# servo.net
KiCad netlist of a schematic drawn in Altium Designer
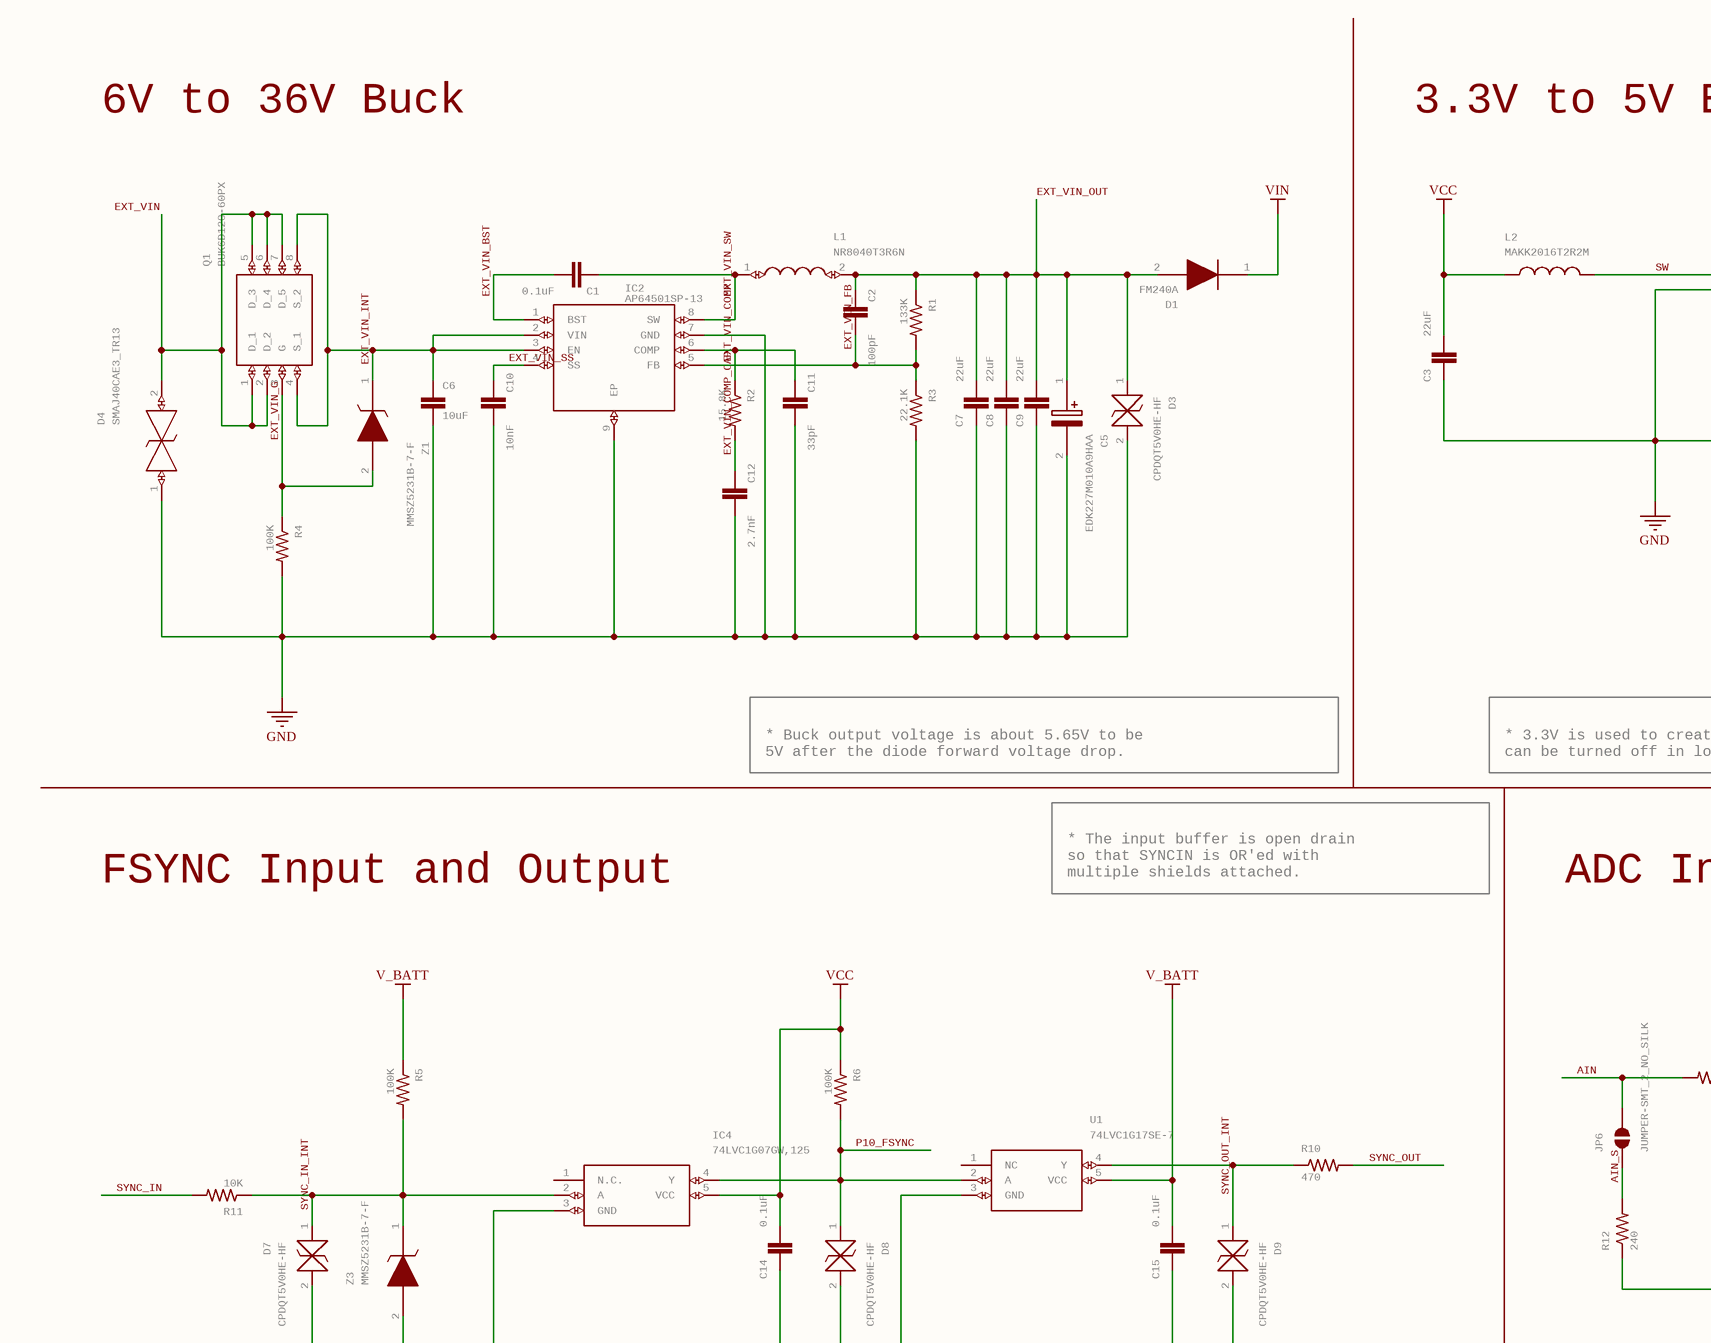
[diagram p0: servo.SchDoc, top left]
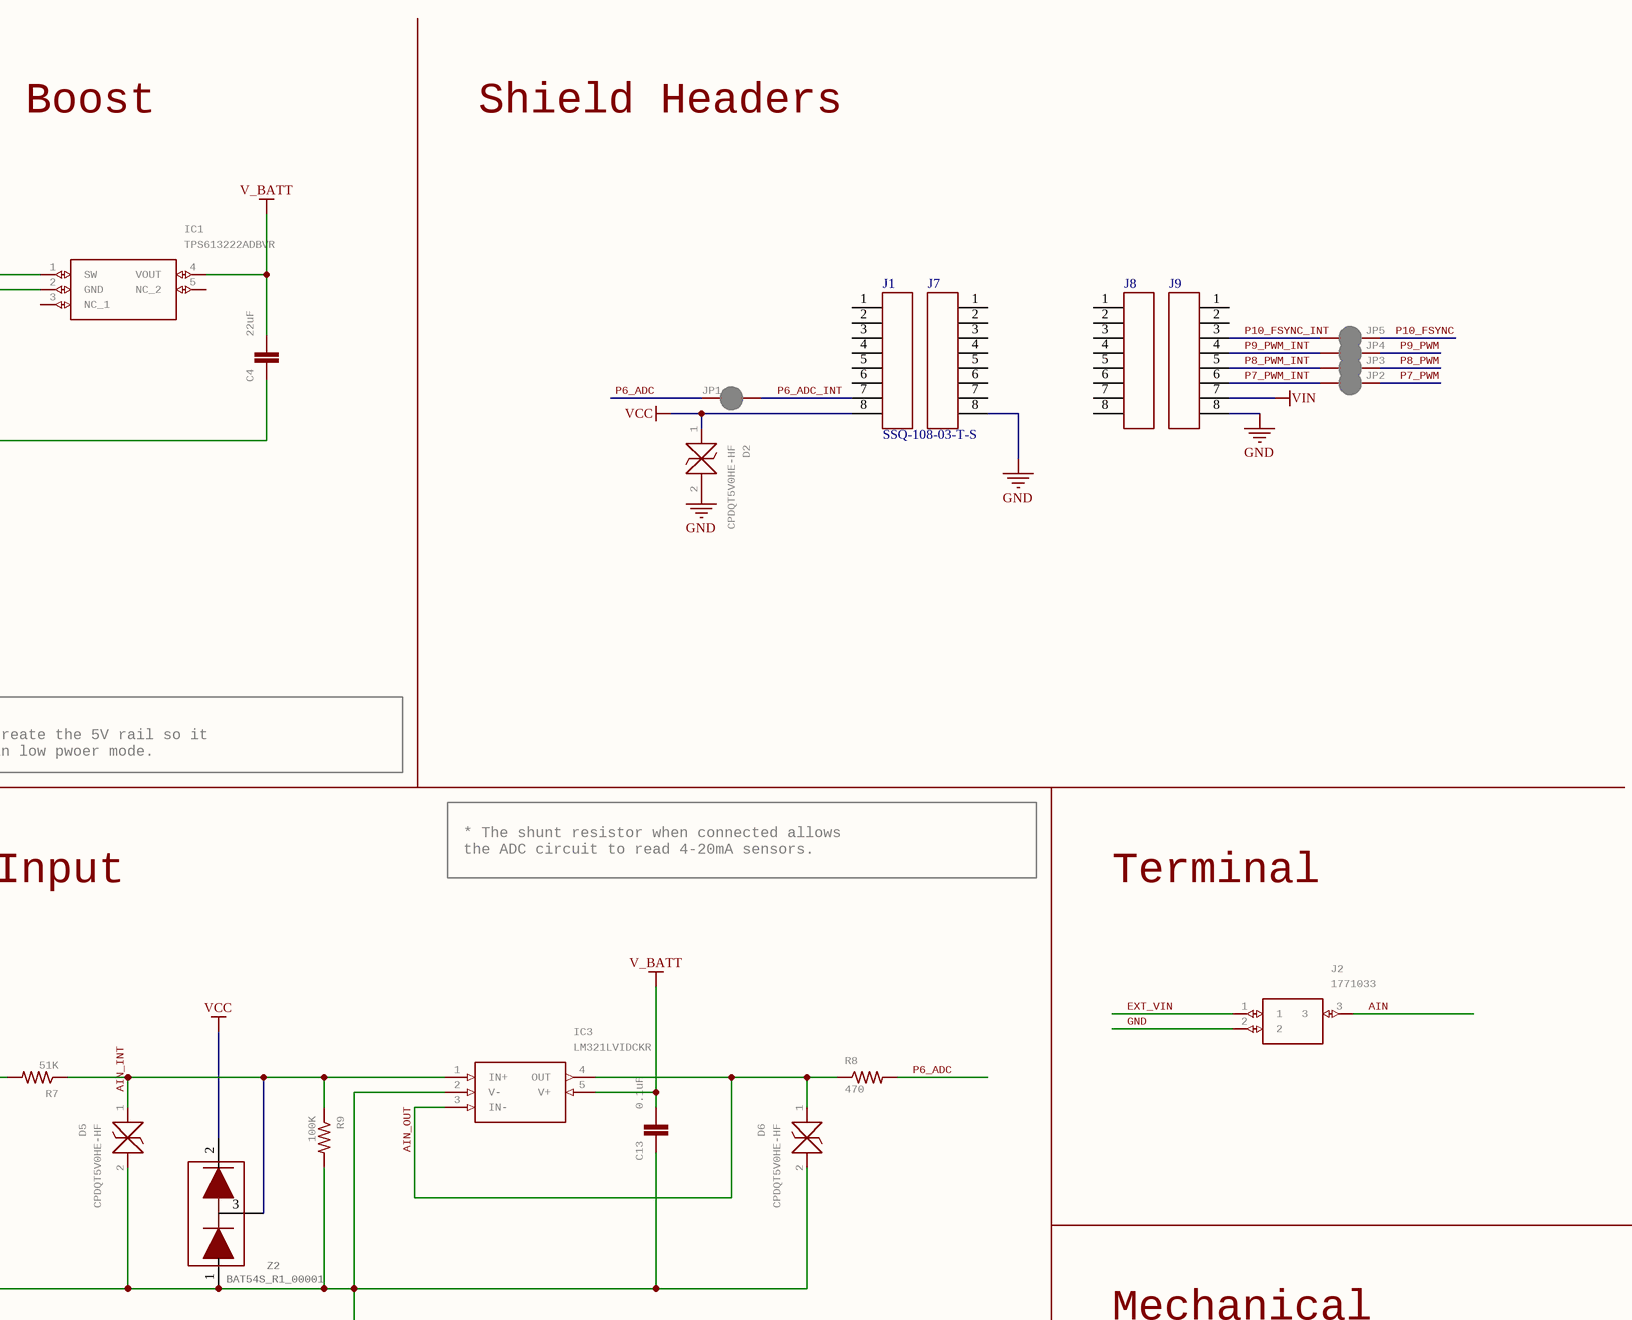
[diagram p1: servo.SchDoc, top right]
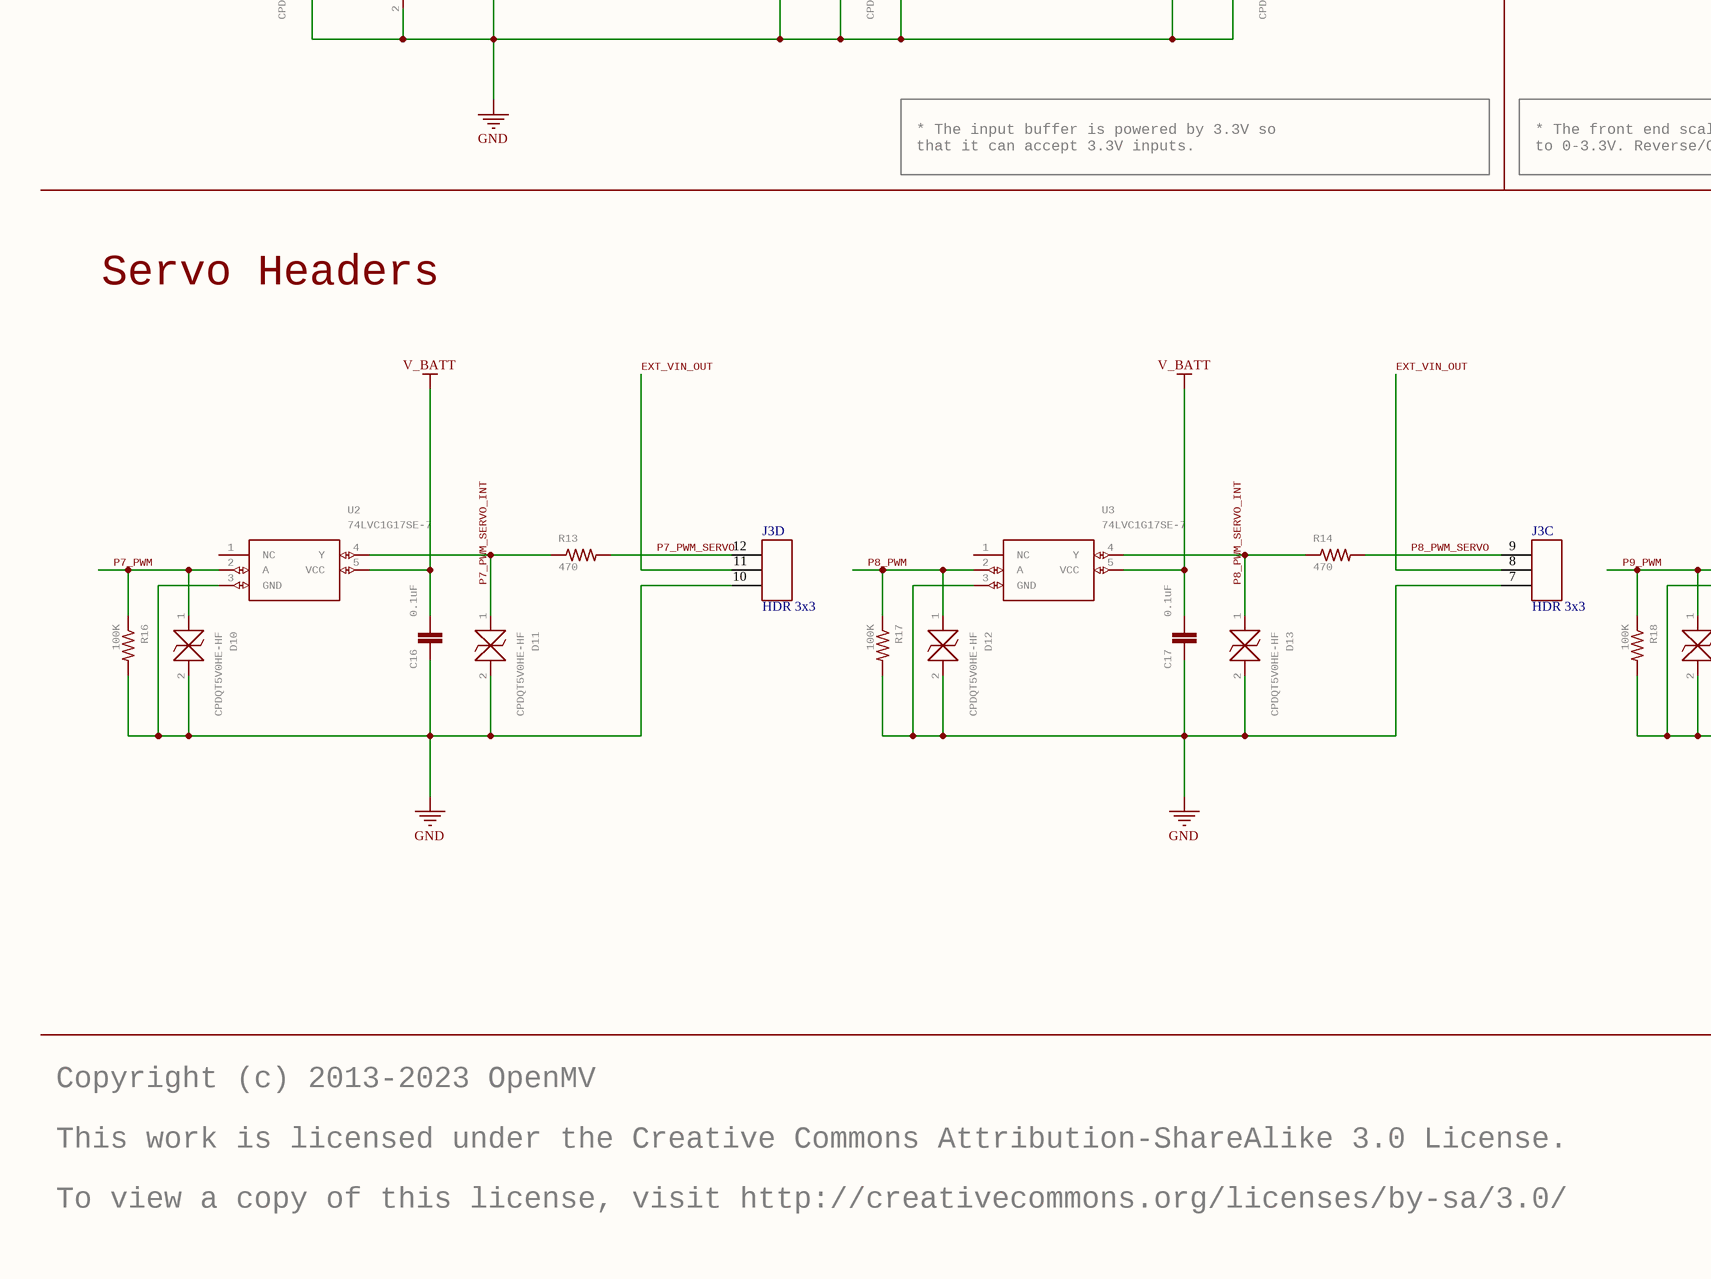
[diagram p2: servo.SchDoc, bottom left]
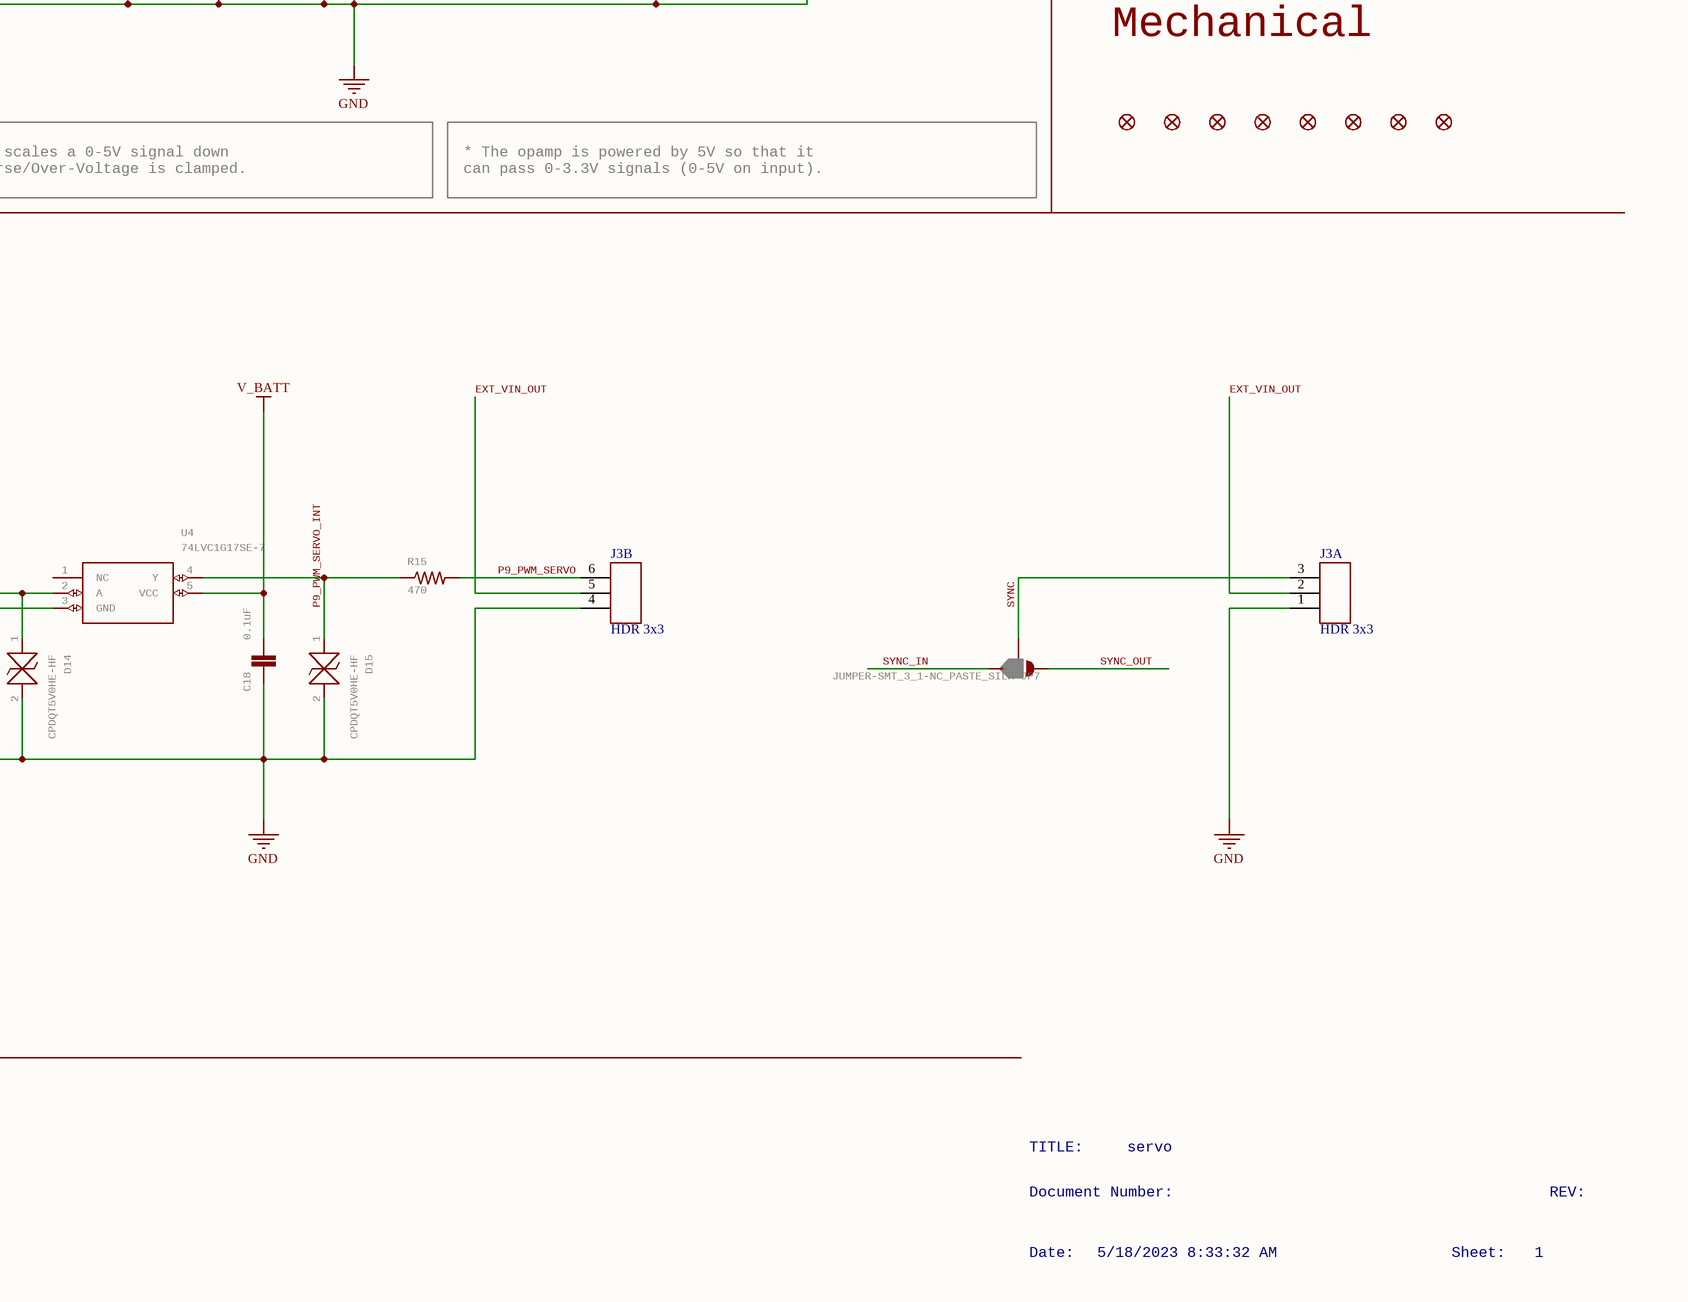
[diagram p3: servo.SchDoc, bottom right]

(export (version "E")
  (design (tool "Eeschema 10.0.6"))
  (components
    (comp (ref "C1")
      (value "0.1uF")
      (footprint "0402-CAP")
      (description "0402 (1005 Metric) Nick Garner - TeleSense")
      (fields (field (name "MPN") "GRM155R71H104KE14D"))
      (libsource (lib "") (part "CAP_0402_1"))
    )
    (comp (ref "C2")
      (value "100pF")
      (footprint "0402-CAP")
      (description "0402 (1005 Metric) Nick Garner - TeleSense")
      (fields (field (name "MPN") "CC0402JRNPO9BN101"))
      (libsource (lib "") (part "CAP_0402_2"))
    )
    (comp (ref "C3")
      (value "22uF")
      (footprint "0805-CAP")
      (fields (field (name "MPN") "CL21A226MQQNNNE"))
      (libsource (lib "SparkFun-Capacitors") (part "22UF-0805-6.3V-20%"))
    )
    (comp (ref "C4")
      (value "22uF")
      (footprint "0805-CAP")
      (fields (field (name "MPN") "CL21A226MQQNNNE"))
      (libsource (lib "SparkFun-Capacitors") (part "22UF-0805-6.3V-20%"))
    )
    (comp (ref "C5")
      (value "EDK227M010A9HAA")
      (footprint "CAPAE660X800N")
      (fields (field (name "MOUSER_PART_NUMBER") "80-EDK227M010A9HAA"))
      (libsource (lib "EDK227M010A9HAA") (part "EDK227M010A9HAA"))
    )
    (comp (ref "C6")
      (value "10uF")
      (footprint "C0805")
      (description "CAPACITOR, European symbol")
      (fields (field (name "MPN") "GRM21BR61H106KE43K"))
      (libsource (lib "rcl") (part "C-EUC0805"))
    )
    (comp (ref "C7")
      (value "22uF")
      (footprint "0805-CAP")
      (fields (field (name "MPN") "CL21A226MQQNNNE"))
      (libsource (lib "SparkFun-Capacitors") (part "22UF-0805-6.3V-20%"))
    )
    (comp (ref "C8")
      (value "22uF")
      (footprint "0805-CAP")
      (fields (field (name "MPN") "CL21A226MQQNNNE"))
      (libsource (lib "SparkFun-Capacitors") (part "22UF-0805-6.3V-20%"))
    )
    (comp (ref "C9")
      (value "22uF")
      (footprint "0805-CAP")
      (fields (field (name "MPN") "CL21A226MQQNNNE"))
      (libsource (lib "SparkFun-Capacitors") (part "22UF-0805-6.3V-20%"))
    )
    (comp (ref "C10")
      (value "10nF")
      (footprint "0402-CAP")
      (description "0402 (1005 Metric) Nick Garner - TeleSense")
      (fields (field (name "MPN") "CL05B103KB5NNNC"))
      (libsource (lib "") (part "CAP_0402_2"))
    )
    (comp (ref "C11")
      (value "33pF")
      (footprint "0402-CAP")
      (description "0402 (1005 Metric) Nick Garner - TeleSense")
      (fields (field (name "MPN") "04025A330JAT2A"))
      (libsource (lib "") (part "CAP_0402_2"))
    )
    (comp (ref "C12")
      (value "2.7nF")
      (footprint "0402-CAP")
      (description "0402 (1005 Metric) Nick Garner - TeleSense")
      (fields (field (name "MPN") "GCM155R71H272KA37J"))
      (libsource (lib "") (part "CAP_0402_2"))
    )
    (comp (ref "C13")
      (value "0.1uF")
      (footprint "0402-CAP")
      (description "0402 (1005 Metric) Nick Garner - TeleSense")
      (fields (field (name "MPN") "GRM155R71H104KE14D"))
      (libsource (lib "0402") (part "CAP_0402"))
    )
    (comp (ref "C14")
      (value "0.1uF")
      (footprint "0402-CAP")
      (description "0402 (1005 Metric) Nick Garner - TeleSense")
      (fields (field (name "MPN") "GRM155R71H104KE14D"))
      (libsource (lib "0402") (part "CAP_0402"))
    )
    (comp (ref "C15")
      (value "0.1uF")
      (footprint "0402-CAP")
      (description "0402 (1005 Metric) Nick Garner - TeleSense")
      (fields (field (name "MPN") "GRM155R71H104KE14D"))
      (libsource (lib "0402") (part "CAP_0402"))
    )
    (comp (ref "C16")
      (value "0.1uF")
      (footprint "0402-CAP")
      (description "0402 (1005 Metric) Nick Garner - TeleSense")
      (fields (field (name "MPN") "GRM155R71H104KE14D"))
      (libsource (lib "0402") (part "CAP_0402"))
    )
    (comp (ref "C17")
      (value "0.1uF")
      (footprint "0402-CAP")
      (description "0402 (1005 Metric) Nick Garner - TeleSense")
      (fields (field (name "MPN") "GRM155R71H104KE14D"))
      (libsource (lib "0402") (part "CAP_0402"))
    )
    (comp (ref "C18")
      (value "0.1uF")
      (footprint "0402-CAP")
      (description "0402 (1005 Metric) Nick Garner - TeleSense")
      (fields (field (name "MPN") "GRM155R71H104KE14D"))
      (libsource (lib "0402") (part "CAP_0402"))
    )
    (comp (ref "D1")
      (value "FM240A")
      (footprint "DIOM5025X231N")
      (description "Diodes - General Purpose, Power, Switching GP Si Rectifier SMB,2A,40V   Source:  Datasheet")
      (fields (field (name "MOUSER_PART_NUMBER") "583-FM240A"))
      (libsource (lib "FM240A") (part "FM240A"))
    )
    (comp (ref "D2")
      (value "CPDQT5V0HE-HF")
      (footprint "CPDQT5V0HEHF")
      (description "ESD Suppressors / TVS Diodes DIODE ESD 5VWM 65W 0402/SOD-923F   Source:  Datasheet")
      (fields (field (name "MOUSER_PART_NUMBER") "MOUSER_PART_NUMBER"))
      (libsource (lib "CPDQT5V0HE-HF") (part "CPDQT5V0HE-HF"))
    )
    (comp (ref "D3")
      (value "CPDQT5V0HE-HF")
      (footprint "CPDQT5V0HEHF")
      (description "ESD Suppressors / TVS Diodes DIODE ESD 5VWM 65W 0402/SOD-923F   Source:  Datasheet")
      (fields (field (name "MOUSER_PART_NUMBER") "MOUSER_PART_NUMBER"))
      (libsource (lib "CPDQT5V0HE-HF") (part "CPDQT5V0HE-HF"))
    )
    (comp (ref "D4")
      (value "SMAJ40CAE3_TR13")
      (footprint "SMAJ40CAE3TR13")
      (description "ESD Suppressors / TVS Diodes TVS   Source:  Datasheet")
      (fields
        (field (name "MANUFACTURER_PART_NUMBER") "SMAJ40CAe3/TR13")
        (field (name "MOUSER_PART_NUMBER") "494-SMAJ40CAE3/TR13")
      )
      (libsource (lib "SMAJ40CAe3_TR13") (part "SMAJ40CAE3_TR13"))
    )
    (comp (ref "D5")
      (value "CPDQT5V0HE-HF")
      (footprint "CPDQT5V0HEHF")
      (description "ESD Suppressors / TVS Diodes DIODE ESD 5VWM 65W 0402/SOD-923F   Source:  Datasheet")
      (fields (field (name "MOUSER_PART_NUMBER") "MOUSER_PART_NUMBER"))
      (libsource (lib "CPDQT5V0HE-HF") (part "CPDQT5V0HE-HF"))
    )
    (comp (ref "D6")
      (value "CPDQT5V0HE-HF")
      (footprint "CPDQT5V0HEHF")
      (description "ESD Suppressors / TVS Diodes DIODE ESD 5VWM 65W 0402/SOD-923F   Source:  Datasheet")
      (fields (field (name "MOUSER_PART_NUMBER") "MOUSER_PART_NUMBER"))
      (libsource (lib "CPDQT5V0HE-HF") (part "CPDQT5V0HE-HF"))
    )
    (comp (ref "D7")
      (value "CPDQT5V0HE-HF")
      (footprint "CPDQT5V0HEHF")
      (description "ESD Suppressors / TVS Diodes DIODE ESD 5VWM 65W 0402/SOD-923F   Source:  Datasheet")
      (fields (field (name "MOUSER_PART_NUMBER") "MOUSER_PART_NUMBER"))
      (libsource (lib "CPDQT5V0HE-HF") (part "CPDQT5V0HE-HF"))
    )
    (comp (ref "D8")
      (value "CPDQT5V0HE-HF")
      (footprint "CPDQT5V0HEHF")
      (description "ESD Suppressors / TVS Diodes DIODE ESD 5VWM 65W 0402/SOD-923F   Source:  Datasheet")
      (fields (field (name "MOUSER_PART_NUMBER") "MOUSER_PART_NUMBER"))
      (libsource (lib "CPDQT5V0HE-HF") (part "CPDQT5V0HE-HF"))
    )
    (comp (ref "D9")
      (value "CPDQT5V0HE-HF")
      (footprint "CPDQT5V0HEHF")
      (description "ESD Suppressors / TVS Diodes DIODE ESD 5VWM 65W 0402/SOD-923F   Source:  Datasheet")
      (fields (field (name "MOUSER_PART_NUMBER") "MOUSER_PART_NUMBER"))
      (libsource (lib "CPDQT5V0HE-HF") (part "CPDQT5V0HE-HF"))
    )
    (comp (ref "D10")
      (value "CPDQT5V0HE-HF")
      (footprint "CPDQT5V0HEHF")
      (description "ESD Suppressors / TVS Diodes DIODE ESD 5VWM 65W 0402/SOD-923F   Source:  Datasheet")
      (fields (field (name "MOUSER_PART_NUMBER") "MOUSER_PART_NUMBER"))
      (libsource (lib "CPDQT5V0HE-HF") (part "CPDQT5V0HE-HF"))
    )
    (comp (ref "D11")
      (value "CPDQT5V0HE-HF")
      (footprint "CPDQT5V0HEHF")
      (description "ESD Suppressors / TVS Diodes DIODE ESD 5VWM 65W 0402/SOD-923F   Source:  Datasheet")
      (fields (field (name "MOUSER_PART_NUMBER") "MOUSER_PART_NUMBER"))
      (libsource (lib "CPDQT5V0HE-HF") (part "CPDQT5V0HE-HF"))
    )
    (comp (ref "D12")
      (value "CPDQT5V0HE-HF")
      (footprint "CPDQT5V0HEHF")
      (description "ESD Suppressors / TVS Diodes DIODE ESD 5VWM 65W 0402/SOD-923F   Source:  Datasheet")
      (fields (field (name "MOUSER_PART_NUMBER") "MOUSER_PART_NUMBER"))
      (libsource (lib "CPDQT5V0HE-HF") (part "CPDQT5V0HE-HF"))
    )
    (comp (ref "D13")
      (value "CPDQT5V0HE-HF")
      (footprint "CPDQT5V0HEHF")
      (description "ESD Suppressors / TVS Diodes DIODE ESD 5VWM 65W 0402/SOD-923F   Source:  Datasheet")
      (fields (field (name "MOUSER_PART_NUMBER") "MOUSER_PART_NUMBER"))
      (libsource (lib "CPDQT5V0HE-HF") (part "CPDQT5V0HE-HF"))
    )
    (comp (ref "D14")
      (value "CPDQT5V0HE-HF")
      (footprint "CPDQT5V0HEHF")
      (description "ESD Suppressors / TVS Diodes DIODE ESD 5VWM 65W 0402/SOD-923F   Source:  Datasheet")
      (fields (field (name "MOUSER_PART_NUMBER") "MOUSER_PART_NUMBER"))
      (libsource (lib "CPDQT5V0HE-HF") (part "CPDQT5V0HE-HF"))
    )
    (comp (ref "D15")
      (value "CPDQT5V0HE-HF")
      (footprint "CPDQT5V0HEHF")
      (description "ESD Suppressors / TVS Diodes DIODE ESD 5VWM 65W 0402/SOD-923F   Source:  Datasheet")
      (fields (field (name "MOUSER_PART_NUMBER") "MOUSER_PART_NUMBER"))
      (libsource (lib "CPDQT5V0HE-HF") (part "CPDQT5V0HE-HF"))
    )
    (comp (ref "FD1")
      (value "FIDUCIAL1X2")
      (footprint "FIDUCIAL-1X2")
      (fields (field (name "LIBRARYNAME") "SparkFun-Aesthetics"))
      (libsource (lib "SparkFun-Aesthetics") (part "FIDUCIAL1X2"))
    )
    (comp (ref "FD2")
      (value "FIDUCIAL1X2")
      (footprint "FIDUCIAL-1X2")
      (fields (field (name "LIBRARYNAME") "SparkFun-Aesthetics"))
      (libsource (lib "SparkFun-Aesthetics") (part "FIDUCIAL1X2"))
    )
    (comp (ref "FD3")
      (value "FIDUCIAL1X2")
      (footprint "FIDUCIAL-1X2")
      (fields (field (name "LIBRARYNAME") "SparkFun-Aesthetics"))
      (libsource (lib "SparkFun-Aesthetics") (part "FIDUCIAL1X2"))
    )
    (comp (ref "FD4")
      (value "FIDUCIAL1X2")
      (footprint "FIDUCIAL-1X2")
      (fields (field (name "LIBRARYNAME") "SparkFun-Aesthetics"))
      (libsource (lib "SparkFun-Aesthetics") (part "FIDUCIAL1X2"))
    )
    (comp (ref "FD5")
      (value "FIDUCIAL1X2")
      (footprint "FIDUCIAL-1X2")
      (fields (field (name "LIBRARYNAME") "SparkFun-Aesthetics"))
      (libsource (lib "SparkFun-Aesthetics") (part "FIDUCIAL1X2"))
    )
    (comp (ref "FD6")
      (value "FIDUCIAL1X2")
      (footprint "FIDUCIAL-1X2")
      (fields (field (name "LIBRARYNAME") "SparkFun-Aesthetics"))
      (libsource (lib "SparkFun-Aesthetics") (part "FIDUCIAL1X2"))
    )
    (comp (ref "FD7")
      (value "FIDUCIAL1X2")
      (footprint "FIDUCIAL-1X2")
      (fields (field (name "LIBRARYNAME") "SparkFun-Aesthetics"))
      (libsource (lib "SparkFun-Aesthetics") (part "FIDUCIAL1X2"))
    )
    (comp (ref "FD8")
      (value "FIDUCIAL1X2")
      (footprint "FIDUCIAL-1X2")
      (fields (field (name "LIBRARYNAME") "SparkFun-Aesthetics"))
      (libsource (lib "SparkFun-Aesthetics") (part "FIDUCIAL1X2"))
    )
    (comp (ref "IC1")
      (value "TPS613222ADBVR")
      (footprint "SOT95P280X145-5N")
      (description "6-uA Quiescent Current, 1.8-A Switch Current Boost Converter   Source:  Datasheet")
      (fields (field (name "MOUSER_PART_NUMBER") "595-TPS613222ADBVR"))
      (libsource (lib "TPS613222ADBVR") (part "TPS613222ADBVR"))
    )
    (comp (ref "IC2")
      (value "AP64501SP-13")
      (footprint "SOIC127P600X163-9N")
      (fields (field (name "MOUSER_PART_NUMBER") "621-AP64501SP-13"))
      (libsource (lib "AP64501SP-13") (part "AP64501SP-13"))
    )
    (comp (ref "IC3")
      (value "LM321LVIDCKR")
      (footprint "SOT65P210X110-5N")
      (description "1-Channel industry standard low voltage operational amplifier   Source:  Datasheet")
      (fields (field (name "MOUSER_PART_NUMBER") "595-LM321LVIDCKR"))
      (libsource (lib "LM321LVIDCKR") (part "LM321LVIDCKR"))
    )
    (comp (ref "IC4")
      (value "74LVC1G07GW,125")
      (footprint "SOT65P212X110-5N")
      (description "74LVC1G07 - Buffer with open-drain output@en-us   Source:  Datasheet")
      (fields (field (name "MOUSER_PART_NUMBER") "771-74LVC1G07GW-G"))
      (libsource (lib "74LVC1G07GW_125") (part "74LVC1G07GW,125"))
    )
    (comp (ref "J1") (value "SSQ-108-03-T-S") (footprint "HDR_1X8") (libsource (lib "pir") (part "HDR_1X8")))
    (comp (ref "J2")
      (value "1771033")
      (footprint "1771033")
      (fields (field (name "MOUSER_PART_NUMBER") "651-1771033"))
      (libsource (lib "1771033") (part "1771033"))
    )
    (comp (ref "J3")
      (value "HDR 3x3")
      (footprint "TSW-104-08-T-T-RA")
      (libsource (lib "rt10") (part "TSW-104-08-T-T-RA"))
    )
    (comp (ref "J7") (value "SSQ-108-03-T-S") (footprint "HDR_1X8") (libsource (lib "") (part "HDR_1X8_1")))
    (comp (ref "J8") (value "SSQ-108-03-T-S") (footprint "HDR_1X8") (libsource (lib "pir") (part "HDR_1X8")))
    (comp (ref "J9") (value "SSQ-108-03-T-S") (footprint "HDR_1X8") (libsource (lib "") (part "HDR_1X8_1")))
    (comp (ref "JP1")
      (value "JUMPER-SMT_2_NC_PASTE_SILK")
      (footprint "SMT-JUMPER_2_NC_PASTE_SILK")
      (libsource (lib "SparkFun-Jumpers") (part "JUMPER-SMT_2_NC_PASTE_SILK"))
    )
    (comp (ref "JP2")
      (value "JUMPER-SMT_2_NC_PASTE_SILK")
      (footprint "SMT-JUMPER_2_NC_PASTE_SILK")
      (libsource (lib "SparkFun-Jumpers") (part "JUMPER-SMT_2_NC_PASTE_SILK"))
    )
    (comp (ref "JP3")
      (value "JUMPER-SMT_2_NC_PASTE_SILK")
      (footprint "SMT-JUMPER_2_NC_PASTE_SILK")
      (libsource (lib "SparkFun-Jumpers") (part "JUMPER-SMT_2_NC_PASTE_SILK"))
    )
    (comp (ref "JP4")
      (value "JUMPER-SMT_2_NC_PASTE_SILK")
      (footprint "SMT-JUMPER_2_NC_PASTE_SILK")
      (libsource (lib "SparkFun-Jumpers") (part "JUMPER-SMT_2_NC_PASTE_SILK"))
    )
    (comp (ref "JP5")
      (value "JUMPER-SMT_2_NC_PASTE_SILK")
      (footprint "SMT-JUMPER_2_NC_PASTE_SILK")
      (libsource (lib "SparkFun-Jumpers") (part "JUMPER-SMT_2_NC_PASTE_SILK"))
    )
    (comp (ref "JP6")
      (value "JUMPER-SMT_2_NO_SILK")
      (footprint "SMT-JUMPER_2_NO_SILK")
      (libsource (lib "SparkFun-Jumpers") (part "JUMPER-SMT_2_NO_SILK"))
    )
    (comp (ref "JP7")
      (value "JUMPER-SMT_3_1-NC_PASTE_SILK")
      (footprint "SMT-JUMPER_3_1-NC_PASTE_SILK")
      (libsource (lib "SparkFun-Jumpers") (part "JUMPER-SMT_3_1-NC_PASTE_SILK"))
    )
    (comp (ref "L1")
      (value "NR8040T3R6N")
      (footprint "NR8040T3R6N")
      (description "NR8040T3R6N   Source:  Datasheet")
      (fields (field (name "MOUSER_PART_NUMBER") "963-NR8040T3R6N") (field (name "MPN") "NRS8040T3R6NJGJ"))
      (libsource (lib "NR8040T3R6N") (part "NR8040T3R6N"))
    )
    (comp (ref "L2")
      (value "MAKK2016T2R2M")
      (footprint "INDC2016X100N")
      (description "INDUCTOR, METAL CORE Check availability")
      (fields (field (name "MF") "Taiyo Yuden"))
      (libsource (lib "MAKK2016T2R2M") (part "MAKK2016T2R2M"))
    )
    (comp (ref "Q1")
      (value "BUK6D120-60PX")
      (footprint "BUK6D12060PX")
      (description "MOSFET 60V P-CH TRENCHMOS SOT1220   Source:  Datasheet")
      (fields (field (name "MOUSER_PART_NUMBER") "771-BUK6D120-60PX"))
      (libsource (lib "BUK6D120-60PX") (part "BUK6D120-60PX"))
    )
    (comp (ref "R1")
      (value "133K")
      (footprint "0402-RES")
      (description "0402 (1005 Metric) Nick Garner - TeleSense")
      (fields (field (name "MPN") "RC0402FR-07133KL"))
      (libsource (lib "0402") (part "RES_0402"))
    )
    (comp (ref "R2")
      (value "15.8K")
      (footprint "0402-RES")
      (description "0402 (1005 Metric) Nick Garner - TeleSense")
      (fields (field (name "MPN") "AC0402FR-0715K8L"))
      (libsource (lib "0402") (part "RES_0402"))
    )
    (comp (ref "R3")
      (value "22.1K")
      (footprint "0402-RES")
      (description "0402 (1005 Metric) Nick Garner - TeleSense")
      (fields (field (name "MPN") "CR0402-FX-2212GLF"))
      (libsource (lib "0402") (part "RES_0402"))
    )
    (comp (ref "R4")
      (value "100K")
      (footprint "0402-RES")
      (description "0402 (1005 Metric) Nick Garner - TeleSense")
      (fields (field (name "MPN") "AC0402FR-07100KL"))
      (libsource (lib "0402") (part "RES_0402"))
    )
    (comp (ref "R5")
      (value "100K")
      (footprint "0402-RES")
      (description "0402 (1005 Metric) Nick Garner - TeleSense")
      (fields (field (name "MPN") "AC0402FR-07100KL"))
      (libsource (lib "0402") (part "RES_0402"))
    )
    (comp (ref "R6")
      (value "100K")
      (footprint "0402-RES")
      (description "0402 (1005 Metric) Nick Garner - TeleSense")
      (fields (field (name "MPN") "AC0402FR-07100KL"))
      (libsource (lib "0402") (part "RES_0402"))
    )
    (comp (ref "R7")
      (value "51K")
      (footprint "0402-RES")
      (description "0402 (1005 Metric) Nick Garner - TeleSense")
      (fields (field (name "MPN") "RC0402JR-0751KL"))
      (libsource (lib "0402") (part "RES_0402"))
    )
    (comp (ref "R8")
      (value "470")
      (footprint "R0603")
      (description "RESISTOR, American symbol")
      (fields (field (name "MPN") "CR0603-FX-4700ELF"))
      (libsource (lib "rcl") (part "R-US_R0603"))
    )
    (comp (ref "R9")
      (value "100K")
      (footprint "0402")
      (description "0402 (1005 Metric) Nick Garner - TeleSense")
      (fields (field (name "MPN") "AC0402FR-07100KL"))
      (libsource (lib "0402") (part "RES_0402"))
    )
    (comp (ref "R10")
      (value "470")
      (footprint "R0603")
      (description "RESISTOR, American symbol")
      (fields (field (name "MPN") "CR0603-FX-4700ELF"))
      (libsource (lib "rcl") (part "R-US_R0603"))
    )
    (comp (ref "R11")
      (value "10K")
      (footprint "0402-RES")
      (description "0402 (1005 Metric) Nick Garner - TeleSense")
      (fields (field (name "MPN") "AC0402FR-1310KL"))
      (libsource (lib "0402") (part "RES_0402"))
    )
    (comp (ref "R12")
      (value "240")
      (footprint "R0603")
      (description "RESISTOR, American symbol")
      (fields (field (name "MPN") "RK73B1JTTD241J"))
      (libsource (lib "rcl") (part "R-US_R0603"))
    )
    (comp (ref "R13")
      (value "470")
      (footprint "R0603")
      (description "RESISTOR, American symbol")
      (fields (field (name "MPN") "CR0603-FX-4700ELF"))
      (libsource (lib "rcl") (part "R-US_R0603"))
    )
    (comp (ref "R14")
      (value "470")
      (footprint "R0603")
      (description "RESISTOR, American symbol")
      (fields (field (name "MPN") "CR0603-FX-4700ELF"))
      (libsource (lib "rcl") (part "R-US_R0603"))
    )
    (comp (ref "R15")
      (value "470")
      (footprint "R0603")
      (description "RESISTOR, American symbol")
      (fields (field (name "MPN") "CR0603-FX-4700ELF"))
      (libsource (lib "rcl") (part "R-US_R0603"))
    )
    (comp (ref "R16")
      (value "100K")
      (footprint "0402-RES")
      (description "0402 (1005 Metric) Nick Garner - TeleSense")
      (fields (field (name "MPN") "AC0402FR-07100KL"))
      (libsource (lib "0402") (part "RES_0402"))
    )
    (comp (ref "R17")
      (value "100K")
      (footprint "0402-RES")
      (description "0402 (1005 Metric) Nick Garner - TeleSense")
      (fields (field (name "MPN") "AC0402FR-07100KL"))
      (libsource (lib "0402") (part "RES_0402"))
    )
    (comp (ref "R18")
      (value "100K")
      (footprint "0402-RES")
      (description "0402 (1005 Metric) Nick Garner - TeleSense")
      (fields (field (name "MPN") "AC0402FR-07100KL"))
      (libsource (lib "0402") (part "RES_0402"))
    )
    (comp (ref "U1")
      (value "74LVC1G17SE-7")
      (footprint "SOT65P210X110-5N")
      (fields (field (name "MOUSER_PART_NUMBER") "621-74LVC1G17SE-7"))
      (libsource (lib "74LVC1G17SE-7") (part "74LVC1G17SE-7"))
    )
    (comp (ref "U2")
      (value "74LVC1G17SE-7")
      (footprint "SOT65P210X110-5N")
      (fields (field (name "MOUSER_PART_NUMBER") "621-74LVC1G17SE-7"))
      (libsource (lib "74LVC1G17SE-7") (part "74LVC1G17SE-7"))
    )
    (comp (ref "U3")
      (value "74LVC1G17SE-7")
      (footprint "SOT65P210X110-5N")
      (fields (field (name "MOUSER_PART_NUMBER") "621-74LVC1G17SE-7"))
      (libsource (lib "74LVC1G17SE-7") (part "74LVC1G17SE-7"))
    )
    (comp (ref "U4")
      (value "74LVC1G17SE-7")
      (footprint "SOT65P210X110-5N")
      (fields (field (name "MOUSER_PART_NUMBER") "621-74LVC1G17SE-7"))
      (libsource (lib "74LVC1G17SE-7") (part "74LVC1G17SE-7"))
    )
    (comp (ref "Z1")
      (value "MMSZ5231B-7-F")
      (footprint "SOD3716X145N")
      (fields (field (name "MOUSER_PART_NUMBER") "621-MMSZ5231B-F"))
      (libsource (lib "MMSZ5231B-7-F") (part "MMSZ5231B-7-F"))
    )
    (comp (ref "Z2")
      (value "BAT54S_R1_00001")
      (footprint "SOT23-3")
      (libsource (lib "can-rs232") (part "BAT54S_R1_00001"))
    )
    (comp (ref "Z3")
      (value "MMSZ5231B-7-F")
      (footprint "SOD3716X145N")
      (fields (field (name "MOUSER_PART_NUMBER") "621-MMSZ5231B-F"))
      (libsource (lib "MMSZ5231B-7-F") (part "MMSZ5231B-7-F"))
    )
  )
  (nets
    (net (code "1") (name "/AIN") (class "Default")
      (node (ref "J2") (pin "3") (pinfunction "3_3") (pintype "bidirectional"))
      (node (ref "JP6") (pin "2") (pinfunction "2_2") (pintype "passive"))
      (node (ref "R7") (pin "2") (pinfunction "2_2") (pintype "passive"))
    )
    (net (code "2") (name "/AIN_INT") (class "Default")
      (node (ref "D5") (pin "1") (pinfunction "1_1") (pintype "bidirectional"))
      (node (ref "IC3") (pin "1") (pinfunction "IN+_1") (pintype "input"))
      (node (ref "R7") (pin "1") (pinfunction "1_1") (pintype "passive"))
      (node (ref "R9") (pin "1") (pinfunction "1_1") (pintype "passive"))
      (node (ref "Z2") (pin "3") (pintype "passive"))
    )
    (net (code "3") (name "/AIN_OUT") (class "Default")
      (node (ref "D6") (pin "1") (pinfunction "1_1") (pintype "bidirectional"))
      (node (ref "IC3") (pin "3") (pinfunction "IN-_3") (pintype "input"))
      (node (ref "IC3") (pin "4") (pinfunction "OUT_4") (pintype "output"))
      (node (ref "R8") (pin "1") (pinfunction "1_1") (pintype "passive"))
    )
    (net (code "4") (name "/AIN_S") (class "Default")
      (node (ref "JP6") (pin "1") (pinfunction "1_1") (pintype "passive"))
      (node (ref "R12") (pin "2") (pinfunction "2_2") (pintype "passive"))
    )
    (net (code "5") (name "/EXT_VIN") (class "Default")
      (node (ref "D4") (pin "2") (pinfunction "2_2") (pintype "bidirectional"))
      (node (ref "J2") (pin "1") (pinfunction "1_1") (pintype "bidirectional"))
      (node (ref "Q1") (pin "1") (pinfunction "D_1_1") (pintype "bidirectional"))
      (node (ref "Q1") (pin "2") (pinfunction "D_2_2") (pintype "bidirectional"))
      (node (ref "Q1") (pin "5") (pinfunction "D_3_5") (pintype "bidirectional"))
      (node (ref "Q1") (pin "6") (pinfunction "D_4_6") (pintype "bidirectional"))
      (node (ref "Q1") (pin "7") (pinfunction "D_5_7") (pintype "bidirectional"))
    )
    (net (code "6") (name "/EXT_VIN_BST") (class "Default")
      (node (ref "C1") (pin "2") (pinfunction "2_2") (pintype "passive"))
      (node (ref "IC2") (pin "1") (pinfunction "BST_1") (pintype "bidirectional"))
    )
    (net (code "7") (name "/EXT_VIN_COMP") (class "Default")
      (node (ref "C11") (pin "1") (pinfunction "1_1") (pintype "passive"))
      (node (ref "IC2") (pin "6") (pinfunction "COMP_6") (pintype "bidirectional"))
      (node (ref "R2") (pin "1") (pinfunction "1_1") (pintype "passive"))
    )
    (net (code "8") (name "/EXT_VIN_COMP_CAP") (class "Default")
      (node (ref "C12") (pin "1") (pinfunction "1_1") (pintype "passive"))
      (node (ref "R2") (pin "2") (pinfunction "2_2") (pintype "passive"))
    )
    (net (code "9") (name "/EXT_VIN_FB") (class "Default")
      (node (ref "C2") (pin "2") (pinfunction "2_2") (pintype "passive"))
      (node (ref "IC2") (pin "5") (pinfunction "FB_5") (pintype "bidirectional"))
      (node (ref "R1") (pin "2") (pinfunction "2_2") (pintype "passive"))
      (node (ref "R3") (pin "1") (pinfunction "1_1") (pintype "passive"))
    )
    (net (code "10") (name "/EXT_VIN_G") (class "Default")
      (node (ref "Q1") (pin "3") (pinfunction "G_3") (pintype "bidirectional"))
      (node (ref "R4") (pin "1") (pinfunction "1_1") (pintype "passive"))
      (node (ref "Z1") (pin "2") (pinfunction "A_2") (pintype "bidirectional"))
    )
    (net (code "11") (name "/EXT_VIN_INT") (class "Default")
      (node (ref "C6") (pin "1") (pinfunction "1_1") (pintype "passive"))
      (node (ref "IC2") (pin "2") (pinfunction "VIN_2") (pintype "bidirectional"))
      (node (ref "IC2") (pin "3") (pinfunction "EN_3") (pintype "bidirectional"))
      (node (ref "Q1") (pin "4") (pinfunction "S_1_4") (pintype "bidirectional"))
      (node (ref "Q1") (pin "8") (pinfunction "S_2_8") (pintype "bidirectional"))
      (node (ref "Z1") (pin "1") (pinfunction "K_1") (pintype "bidirectional"))
    )
    (net (code "12") (name "/EXT_VIN_OUT") (class "Default")
      (node (ref "C2") (pin "1") (pinfunction "1_1") (pintype "passive"))
      (node (ref "C5") (pin "1") (pinfunction "+_1") (pintype "bidirectional"))
      (node (ref "C7") (pin "2") (pinfunction "2_2") (pintype "passive"))
      (node (ref "C8") (pin "2") (pinfunction "2_2") (pintype "passive"))
      (node (ref "C9") (pin "2") (pinfunction "2_2") (pintype "passive"))
      (node (ref "D1") (pin "2") (pinfunction "A_2") (pintype "bidirectional"))
      (node (ref "D3") (pin "1") (pinfunction "1_1") (pintype "bidirectional"))
      (node (ref "J3") (pin "11") (pintype "passive"))
      (node (ref "J3") (pin "2") (pintype "passive"))
      (node (ref "J3") (pin "5") (pintype "passive"))
      (node (ref "J3") (pin "8") (pintype "passive"))
      (node (ref "L1") (pin "2") (pinfunction "2_2") (pintype "bidirectional"))
      (node (ref "R1") (pin "1") (pinfunction "1_1") (pintype "passive"))
    )
    (net (code "13") (name "/EXT_VIN_SS") (class "Default")
      (node (ref "C10") (pin "1") (pinfunction "1_1") (pintype "passive"))
      (node (ref "IC2") (pin "4") (pinfunction "SS_4") (pintype "bidirectional"))
    )
    (net (code "14") (name "/EXT_VIN_SW") (class "Default")
      (node (ref "C1") (pin "1") (pinfunction "1_1") (pintype "passive"))
      (node (ref "IC2") (pin "8") (pinfunction "SW_8") (pintype "bidirectional"))
      (node (ref "L1") (pin "1") (pinfunction "1_1") (pintype "bidirectional"))
    )
    (net (code "15") (name "/P6_ADC") (class "Default")
      (node (ref "JP1") (pin "2") (pinfunction "2_2") (pintype "passive"))
      (node (ref "R8") (pin "2") (pinfunction "2_2") (pintype "passive"))
    )
    (net (code "16") (name "/P6_ADC_INT") (class "Default")
      (node (ref "J1") (pin "7") (pintype "passive"))
      (node (ref "JP1") (pin "1") (pinfunction "1_1") (pintype "passive"))
    )
    (net (code "17") (name "/P7_PWM") (class "Default")
      (node (ref "D10") (pin "1") (pinfunction "1_1") (pintype "bidirectional"))
      (node (ref "JP2") (pin "2") (pinfunction "2_2") (pintype "passive"))
      (node (ref "R16") (pin "1") (pinfunction "1_1") (pintype "passive"))
      (node (ref "U2") (pin "2") (pinfunction "A_2") (pintype "bidirectional"))
    )
    (net (code "18") (name "/P7_PWM_INT") (class "Default")
      (node (ref "J9") (pin "6") (pintype "passive"))
      (node (ref "JP2") (pin "1") (pinfunction "1_1") (pintype "passive"))
    )
    (net (code "19") (name "/P7_PWM_SERVO") (class "Default")
      (node (ref "J3") (pin "12") (pintype "passive"))
      (node (ref "R13") (pin "2") (pinfunction "2_2") (pintype "passive"))
    )
    (net (code "20") (name "/P7_PWM_SERVO_INT") (class "Default")
      (node (ref "D11") (pin "1") (pinfunction "1_1") (pintype "bidirectional"))
      (node (ref "R13") (pin "1") (pinfunction "1_1") (pintype "passive"))
      (node (ref "U2") (pin "4") (pinfunction "Y_4") (pintype "bidirectional"))
    )
    (net (code "21") (name "/P8_PWM") (class "Default")
      (node (ref "D12") (pin "1") (pinfunction "1_1") (pintype "bidirectional"))
      (node (ref "JP3") (pin "2") (pinfunction "2_2") (pintype "passive"))
      (node (ref "R17") (pin "1") (pinfunction "1_1") (pintype "passive"))
      (node (ref "U3") (pin "2") (pinfunction "A_2") (pintype "bidirectional"))
    )
    (net (code "22") (name "/P8_PWM_INT") (class "Default")
      (node (ref "J9") (pin "5") (pintype "passive"))
      (node (ref "JP3") (pin "1") (pinfunction "1_1") (pintype "passive"))
    )
    (net (code "23") (name "/P8_PWM_SERVO") (class "Default")
      (node (ref "J3") (pin "9") (pintype "passive"))
      (node (ref "R14") (pin "2") (pinfunction "2_2") (pintype "passive"))
    )
    (net (code "24") (name "/P8_PWM_SERVO_INT") (class "Default")
      (node (ref "D13") (pin "1") (pinfunction "1_1") (pintype "bidirectional"))
      (node (ref "R14") (pin "1") (pinfunction "1_1") (pintype "passive"))
      (node (ref "U3") (pin "4") (pinfunction "Y_4") (pintype "bidirectional"))
    )
    (net (code "25") (name "/P9_PWM") (class "Default")
      (node (ref "D14") (pin "1") (pinfunction "1_1") (pintype "bidirectional"))
      (node (ref "JP4") (pin "2") (pinfunction "2_2") (pintype "passive"))
      (node (ref "R18") (pin "1") (pinfunction "1_1") (pintype "passive"))
      (node (ref "U4") (pin "2") (pinfunction "A_2") (pintype "bidirectional"))
    )
    (net (code "26") (name "/P9_PWM_INT") (class "Default")
      (node (ref "J9") (pin "4") (pintype "passive"))
      (node (ref "JP4") (pin "1") (pinfunction "1_1") (pintype "passive"))
    )
    (net (code "27") (name "/P9_PWM_SERVO") (class "Default")
      (node (ref "J3") (pin "6") (pintype "passive"))
      (node (ref "R15") (pin "2") (pinfunction "2_2") (pintype "passive"))
    )
    (net (code "28") (name "/P9_PWM_SERVO_INT") (class "Default")
      (node (ref "D15") (pin "1") (pinfunction "1_1") (pintype "bidirectional"))
      (node (ref "R15") (pin "1") (pinfunction "1_1") (pintype "passive"))
      (node (ref "U4") (pin "4") (pinfunction "Y_4") (pintype "bidirectional"))
    )
    (net (code "29") (name "/P10_FSYNC") (class "Default")
      (node (ref "D8") (pin "1") (pinfunction "1_1") (pintype "bidirectional"))
      (node (ref "IC4") (pin "4") (pinfunction "Y_4") (pintype "bidirectional"))
      (node (ref "JP5") (pin "2") (pinfunction "2_2") (pintype "passive"))
      (node (ref "R6") (pin "2") (pinfunction "2_2") (pintype "passive"))
      (node (ref "U1") (pin "2") (pinfunction "A_2") (pintype "bidirectional"))
    )
    (net (code "30") (name "/P10_FSYNC_INT") (class "Default")
      (node (ref "J9") (pin "3") (pintype "passive"))
      (node (ref "JP5") (pin "1") (pinfunction "1_1") (pintype "passive"))
    )
    (net (code "31") (name "/SW") (class "Default")
      (node (ref "IC1") (pin "1") (pinfunction "SW_1") (pintype "bidirectional"))
      (node (ref "L2") (pin "2") (pinfunction "2_2") (pintype "passive"))
    )
    (net (code "32") (name "/SYNC") (class "Default")
      (node (ref "J3") (pin "3") (pintype "passive"))
      (node (ref "JP7") (pin "2") (pinfunction "2_2") (pintype "passive"))
    )
    (net (code "33") (name "/SYNC_IN") (class "Default")
      (node (ref "JP7") (pin "3") (pinfunction "3_3") (pintype "passive"))
      (node (ref "R11") (pin "2") (pinfunction "2_2") (pintype "passive"))
    )
    (net (code "34") (name "/SYNC_IN_INT") (class "Default")
      (node (ref "D7") (pin "1") (pinfunction "1_1") (pintype "bidirectional"))
      (node (ref "IC4") (pin "2") (pinfunction "A_2") (pintype "bidirectional"))
      (node (ref "R11") (pin "1") (pinfunction "1_1") (pintype "passive"))
      (node (ref "R5") (pin "2") (pinfunction "2_2") (pintype "passive"))
      (node (ref "Z3") (pin "1") (pinfunction "K_1") (pintype "bidirectional"))
    )
    (net (code "35") (name "/SYNC_OUT") (class "Default")
      (node (ref "JP7") (pin "1") (pinfunction "1_1") (pintype "passive"))
      (node (ref "R10") (pin "2") (pinfunction "2_2") (pintype "passive"))
    )
    (net (code "36") (name "/SYNC_OUT_INT") (class "Default")
      (node (ref "D9") (pin "1") (pinfunction "1_1") (pintype "bidirectional"))
      (node (ref "R10") (pin "1") (pinfunction "1_1") (pintype "passive"))
      (node (ref "U1") (pin "4") (pinfunction "Y_4") (pintype "bidirectional"))
    )
    (net (code "37") (name "GND") (class "Default")
      (node (ref "C10") (pin "2") (pinfunction "2_2") (pintype "passive"))
      (node (ref "C11") (pin "2") (pinfunction "2_2") (pintype "passive"))
      (node (ref "C12") (pin "2") (pinfunction "2_2") (pintype "passive"))
      (node (ref "C13") (pin "1") (pinfunction "1_1") (pintype "passive"))
      (node (ref "C14") (pin "1") (pinfunction "1_1") (pintype "passive"))
      (node (ref "C15") (pin "1") (pinfunction "1_1") (pintype "passive"))
      (node (ref "C16") (pin "1") (pinfunction "1_1") (pintype "passive"))
      (node (ref "C17") (pin "1") (pinfunction "1_1") (pintype "passive"))
      (node (ref "C18") (pin "1") (pinfunction "1_1") (pintype "passive"))
      (node (ref "C3") (pin "1") (pinfunction "1_1") (pintype "passive"))
      (node (ref "C4") (pin "1") (pinfunction "1_1") (pintype "passive"))
      (node (ref "C5") (pin "2") (pinfunction "-_2") (pintype "bidirectional"))
      (node (ref "C6") (pin "2") (pinfunction "2_2") (pintype "passive"))
      (node (ref "C7") (pin "1") (pinfunction "1_1") (pintype "passive"))
      (node (ref "C8") (pin "1") (pinfunction "1_1") (pintype "passive"))
      (node (ref "C9") (pin "1") (pinfunction "1_1") (pintype "passive"))
      (node (ref "D10") (pin "2") (pinfunction "2_2") (pintype "bidirectional"))
      (node (ref "D11") (pin "2") (pinfunction "2_2") (pintype "bidirectional"))
      (node (ref "D12") (pin "2") (pinfunction "2_2") (pintype "bidirectional"))
      (node (ref "D13") (pin "2") (pinfunction "2_2") (pintype "bidirectional"))
      (node (ref "D14") (pin "2") (pinfunction "2_2") (pintype "bidirectional"))
      (node (ref "D15") (pin "2") (pinfunction "2_2") (pintype "bidirectional"))
      (node (ref "D2") (pin "2") (pinfunction "2_2") (pintype "bidirectional"))
      (node (ref "D3") (pin "2") (pinfunction "2_2") (pintype "bidirectional"))
      (node (ref "D4") (pin "1") (pinfunction "1_1") (pintype "bidirectional"))
      (node (ref "D5") (pin "2") (pinfunction "2_2") (pintype "bidirectional"))
      (node (ref "D6") (pin "2") (pinfunction "2_2") (pintype "bidirectional"))
      (node (ref "D7") (pin "2") (pinfunction "2_2") (pintype "bidirectional"))
      (node (ref "D8") (pin "2") (pinfunction "2_2") (pintype "bidirectional"))
      (node (ref "D9") (pin "2") (pinfunction "2_2") (pintype "bidirectional"))
      (node (ref "IC1") (pin "2") (pinfunction "GND_2") (pintype "bidirectional"))
      (node (ref "IC2") (pin "7") (pinfunction "GND_7") (pintype "bidirectional"))
      (node (ref "IC2") (pin "9") (pinfunction "EP_9") (pintype "bidirectional"))
      (node (ref "IC3") (pin "2") (pinfunction "V-_2") (pintype "input"))
      (node (ref "IC4") (pin "3") (pinfunction "GND_3") (pintype "bidirectional"))
      (node (ref "J2") (pin "2") (pinfunction "2_2") (pintype "bidirectional"))
      (node (ref "J3") (pin "1") (pintype "passive"))
      (node (ref "J3") (pin "10") (pintype "passive"))
      (node (ref "J3") (pin "4") (pintype "passive"))
      (node (ref "J3") (pin "7") (pintype "passive"))
      (node (ref "J7") (pin "8") (pintype "passive"))
      (node (ref "J9") (pin "8") (pintype "passive"))
      (node (ref "R12") (pin "1") (pinfunction "1_1") (pintype "passive"))
      (node (ref "R16") (pin "2") (pinfunction "2_2") (pintype "passive"))
      (node (ref "R17") (pin "2") (pinfunction "2_2") (pintype "passive"))
      (node (ref "R18") (pin "2") (pinfunction "2_2") (pintype "passive"))
      (node (ref "R3") (pin "2") (pinfunction "2_2") (pintype "passive"))
      (node (ref "R4") (pin "2") (pinfunction "2_2") (pintype "passive"))
      (node (ref "R9") (pin "2") (pinfunction "2_2") (pintype "passive"))
      (node (ref "U1") (pin "3") (pinfunction "GND_3") (pintype "bidirectional"))
      (node (ref "U2") (pin "3") (pinfunction "GND_3") (pintype "bidirectional"))
      (node (ref "U3") (pin "3") (pinfunction "GND_3") (pintype "bidirectional"))
      (node (ref "U4") (pin "3") (pinfunction "GND_3") (pintype "bidirectional"))
      (node (ref "Z2") (pin "1") (pintype "passive"))
      (node (ref "Z3") (pin "2") (pinfunction "A_2") (pintype "bidirectional"))
    )
    (net (code "38") (name "VCC") (class "Default")
      (node (ref "C14") (pin "2") (pinfunction "2_2") (pintype "passive"))
      (node (ref "C3") (pin "2") (pinfunction "2_2") (pintype "passive"))
      (node (ref "D2") (pin "1") (pinfunction "1_1") (pintype "bidirectional"))
      (node (ref "IC4") (pin "5") (pinfunction "VCC_5") (pintype "bidirectional"))
      (node (ref "J1") (pin "8") (pintype "passive"))
      (node (ref "L2") (pin "1") (pinfunction "1_1") (pintype "passive"))
      (node (ref "R6") (pin "1") (pinfunction "1_1") (pintype "passive"))
      (node (ref "Z2") (pin "2") (pintype "passive"))
    )
    (net (code "39") (name "VIN") (class "Default")
      (node (ref "D1") (pin "1") (pinfunction "K_1") (pintype "bidirectional"))
      (node (ref "J9") (pin "7") (pintype "passive"))
    )
    (net (code "40") (name "V_BATT") (class "Default")
      (node (ref "C13") (pin "2") (pinfunction "2_2") (pintype "passive"))
      (node (ref "C15") (pin "2") (pinfunction "2_2") (pintype "passive"))
      (node (ref "C16") (pin "2") (pinfunction "2_2") (pintype "passive"))
      (node (ref "C17") (pin "2") (pinfunction "2_2") (pintype "passive"))
      (node (ref "C18") (pin "2") (pinfunction "2_2") (pintype "passive"))
      (node (ref "C4") (pin "2") (pinfunction "2_2") (pintype "passive"))
      (node (ref "IC1") (pin "4") (pinfunction "VOUT_4") (pintype "bidirectional"))
      (node (ref "IC3") (pin "5") (pinfunction "V+_5") (pintype "input"))
      (node (ref "R5") (pin "1") (pinfunction "1_1") (pintype "passive"))
      (node (ref "U1") (pin "5") (pinfunction "VCC_5") (pintype "bidirectional"))
      (node (ref "U2") (pin "5") (pinfunction "VCC_5") (pintype "bidirectional"))
      (node (ref "U3") (pin "5") (pinfunction "VCC_5") (pintype "bidirectional"))
      (node (ref "U4") (pin "5") (pinfunction "VCC_5") (pintype "bidirectional"))
    )
    (net (code "41") (name "unconnected-(IC1-NC_1-Pad3)") (class "Default")
      (node (ref "IC1") (pin "3") (pinfunction "NC_1_3") (pintype "bidirectional"))
    )
    (net (code "42") (name "unconnected-(IC1-NC_2-Pad5)") (class "Default")
      (node (ref "IC1") (pin "5") (pinfunction "NC_2_5") (pintype "bidirectional"))
    )
    (net (code "43") (name "unconnected-(IC4-N.C.-Pad1)") (class "Default")
      (node (ref "IC4") (pin "1") (pinfunction "N.C._1") (pintype "passive"))
    )
    (net (code "44") (name "unconnected-(J1-Pad1)") (class "Default")
      (node (ref "J1") (pin "1") (pintype "passive"))
    )
    (net (code "45") (name "unconnected-(J1-Pad2)") (class "Default")
      (node (ref "J1") (pin "2") (pintype "passive"))
    )
    (net (code "46") (name "unconnected-(J1-Pad3)") (class "Default")
      (node (ref "J1") (pin "3") (pintype "passive"))
    )
    (net (code "47") (name "unconnected-(J1-Pad4)") (class "Default")
      (node (ref "J1") (pin "4") (pintype "passive"))
    )
    (net (code "48") (name "unconnected-(J1-Pad5)") (class "Default")
      (node (ref "J1") (pin "5") (pintype "passive"))
    )
    (net (code "49") (name "unconnected-(J1-Pad6)") (class "Default")
      (node (ref "J1") (pin "6") (pintype "passive"))
    )
    (net (code "50") (name "unconnected-(J7-Pad1)") (class "Default")
      (node (ref "J7") (pin "1") (pintype "passive"))
    )
    (net (code "51") (name "unconnected-(J7-Pad2)") (class "Default")
      (node (ref "J7") (pin "2") (pintype "passive"))
    )
    (net (code "52") (name "unconnected-(J7-Pad3)") (class "Default")
      (node (ref "J7") (pin "3") (pintype "passive"))
    )
    (net (code "53") (name "unconnected-(J7-Pad4)") (class "Default")
      (node (ref "J7") (pin "4") (pintype "passive"))
    )
    (net (code "54") (name "unconnected-(J7-Pad5)") (class "Default")
      (node (ref "J7") (pin "5") (pintype "passive"))
    )
    (net (code "55") (name "unconnected-(J7-Pad6)") (class "Default")
      (node (ref "J7") (pin "6") (pintype "passive"))
    )
    (net (code "56") (name "unconnected-(J7-Pad7)") (class "Default")
      (node (ref "J7") (pin "7") (pintype "passive"))
    )
    (net (code "57") (name "unconnected-(J8-Pad1)") (class "Default")
      (node (ref "J8") (pin "1") (pintype "passive"))
    )
    (net (code "58") (name "unconnected-(J8-Pad2)") (class "Default")
      (node (ref "J8") (pin "2") (pintype "passive"))
    )
    (net (code "59") (name "unconnected-(J8-Pad3)") (class "Default")
      (node (ref "J8") (pin "3") (pintype "passive"))
    )
    (net (code "60") (name "unconnected-(J8-Pad4)") (class "Default")
      (node (ref "J8") (pin "4") (pintype "passive"))
    )
    (net (code "61") (name "unconnected-(J8-Pad5)") (class "Default")
      (node (ref "J8") (pin "5") (pintype "passive"))
    )
    (net (code "62") (name "unconnected-(J8-Pad6)") (class "Default")
      (node (ref "J8") (pin "6") (pintype "passive"))
    )
    (net (code "63") (name "unconnected-(J8-Pad7)") (class "Default")
      (node (ref "J8") (pin "7") (pintype "passive"))
    )
    (net (code "64") (name "unconnected-(J8-Pad8)") (class "Default")
      (node (ref "J8") (pin "8") (pintype "passive"))
    )
    (net (code "65") (name "unconnected-(J9-Pad1)") (class "Default")
      (node (ref "J9") (pin "1") (pintype "passive"))
    )
    (net (code "66") (name "unconnected-(J9-Pad2)") (class "Default")
      (node (ref "J9") (pin "2") (pintype "passive"))
    )
    (net (code "67") (name "unconnected-(U1-NC-Pad1)") (class "Default")
      (node (ref "U1") (pin "1") (pinfunction "NC_1") (pintype "passive"))
    )
    (net (code "68") (name "unconnected-(U2-NC-Pad1)") (class "Default")
      (node (ref "U2") (pin "1") (pinfunction "NC_1") (pintype "passive"))
    )
    (net (code "69") (name "unconnected-(U3-NC-Pad1)") (class "Default")
      (node (ref "U3") (pin "1") (pinfunction "NC_1") (pintype "passive"))
    )
    (net (code "70") (name "unconnected-(U4-NC-Pad1)") (class "Default")
      (node (ref "U4") (pin "1") (pinfunction "NC_1") (pintype "passive"))
    )
  )
)
